# Sensors.net
KiCad netlist of a schematic drawn in Altium Designer
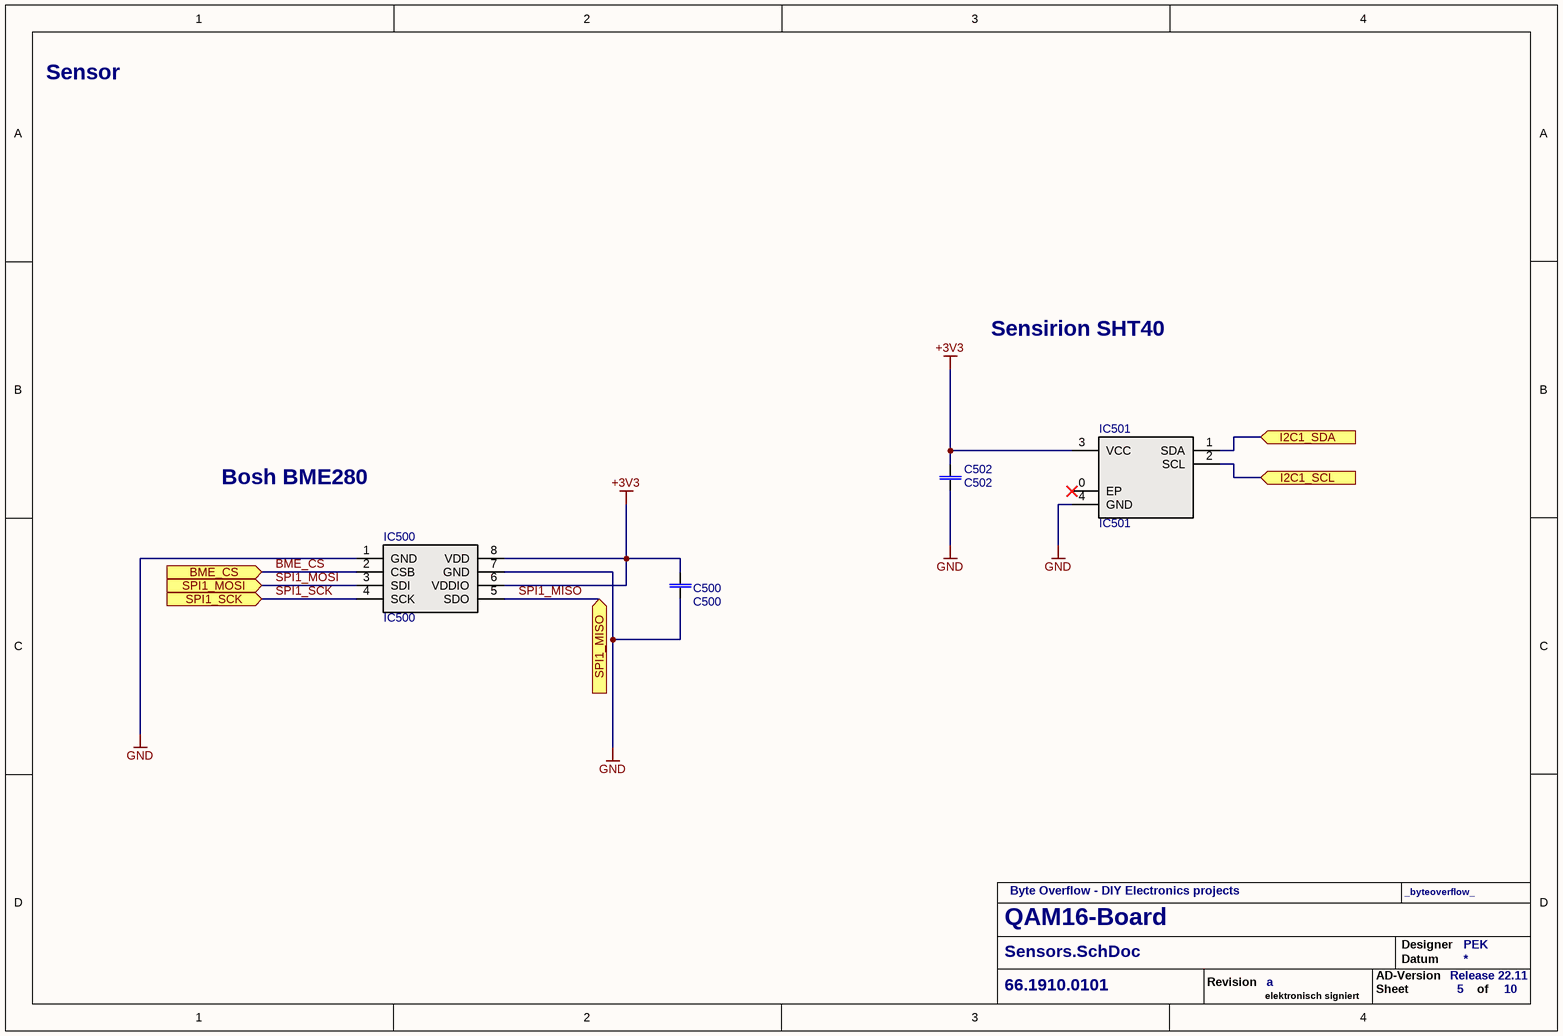
[diagram p0: Sensors.SchDoc]

(export (version "E")
  (design (tool "Eeschema 10.0.6"))
  (components
    (comp (ref "C500")
      (value "C 100nF 50V X7R")
      (footprint "0603-1608")
      (description "Capacitor")
      (fields
        (field (name "MANUFACTURER") "KEMET")
        (field (name "MANUFACTURER PART NUMBER") "C0603C104K5RACTU")
      )
      (libsource (lib "Database_Libs1") (part "Kondensator"))
    )
    (comp (ref "C502")
      (value "C 100nF 50V X7R")
      (footprint "0603-1608")
      (description "Capacitor")
      (fields
        (field (name "MANUFACTURER") "KEMET")
        (field (name "MANUFACTURER PART NUMBER") "C0603C104K5RACTU")
      )
      (libsource (lib "Database_Libs1") (part "Kondensator"))
    )
    (comp (ref "IC500")
      (value "BME280")
      (footprint "LGA-8 2.5x2.5x0.95")
      (description "Sensor")
      (fields (field (name "MANUFACTURER") "Bosch Sensortec"))
      (libsource (lib "Database_Libs1") (part "BMEx80"))
    )
    (comp (ref "IC501")
      (value "SHT40-AD1B-R2")
      (footprint "XDCR_SHT40-AD1B-R2")
      (description "Sensor")
      (fields (field (name "MANUFACTURER") "Sensirion"))
      (libsource (lib "Database_Libs1") (part "SHT4x"))
    )
  )
  (nets
    (net (code "1") (name "+3V3") (class "Default")
      (node (ref "C500") (pin "1") (pinfunction "1_1") (pintype "passive"))
      (node (ref "C502") (pin "1") (pinfunction "1_1") (pintype "passive"))
      (node (ref "IC500") (pin "6") (pinfunction "VDDIO_6") (pintype "passive"))
      (node (ref "IC500") (pin "8") (pinfunction "VDD_8") (pintype "passive"))
      (node (ref "IC501") (pin "3") (pinfunction "VCC_3") (pintype "passive"))
    )
    (net (code "2") (name "/BME_CS") (class "Default")
      (node (ref "IC500") (pin "2") (pinfunction "CSB_2") (pintype "passive"))
    )
    (net (code "3") (name "/I2C1_SCL") (class "Default")
      (node (ref "IC501") (pin "2") (pinfunction "SCL_2") (pintype "passive"))
    )
    (net (code "4") (name "/I2C1_SDA") (class "Default")
      (node (ref "IC501") (pin "1") (pinfunction "SDA_1") (pintype "passive"))
    )
    (net (code "5") (name "/SPI1_MISO") (class "Default")
      (node (ref "IC500") (pin "5") (pinfunction "SDO_5") (pintype "passive"))
    )
    (net (code "6") (name "/SPI1_MOSI") (class "Default")
      (node (ref "IC500") (pin "3") (pinfunction "SDI_3") (pintype "passive"))
    )
    (net (code "7") (name "/SPI1_SCK") (class "Default")
      (node (ref "IC500") (pin "4") (pinfunction "SCK_4") (pintype "passive"))
    )
    (net (code "8") (name "GND") (class "Default")
      (node (ref "C500") (pin "2") (pinfunction "2_2") (pintype "passive"))
      (node (ref "C502") (pin "2") (pinfunction "2_2") (pintype "passive"))
      (node (ref "IC500") (pin "1") (pinfunction "GND_1") (pintype "passive"))
      (node (ref "IC500") (pin "7") (pinfunction "GND_7") (pintype "passive"))
      (node (ref "IC501") (pin "4") (pinfunction "GND_4") (pintype "passive"))
    )
    (net (code "9") (name "unconnected-(IC501-EP-Pad0)") (class "Default")
      (node (ref "IC501") (pin "0") (pinfunction "EP_0") (pintype "passive+no_connect"))
    )
  )
)
